# Extruder_1_Board.net
KiCad netlist of a schematic drawn in EAGLE
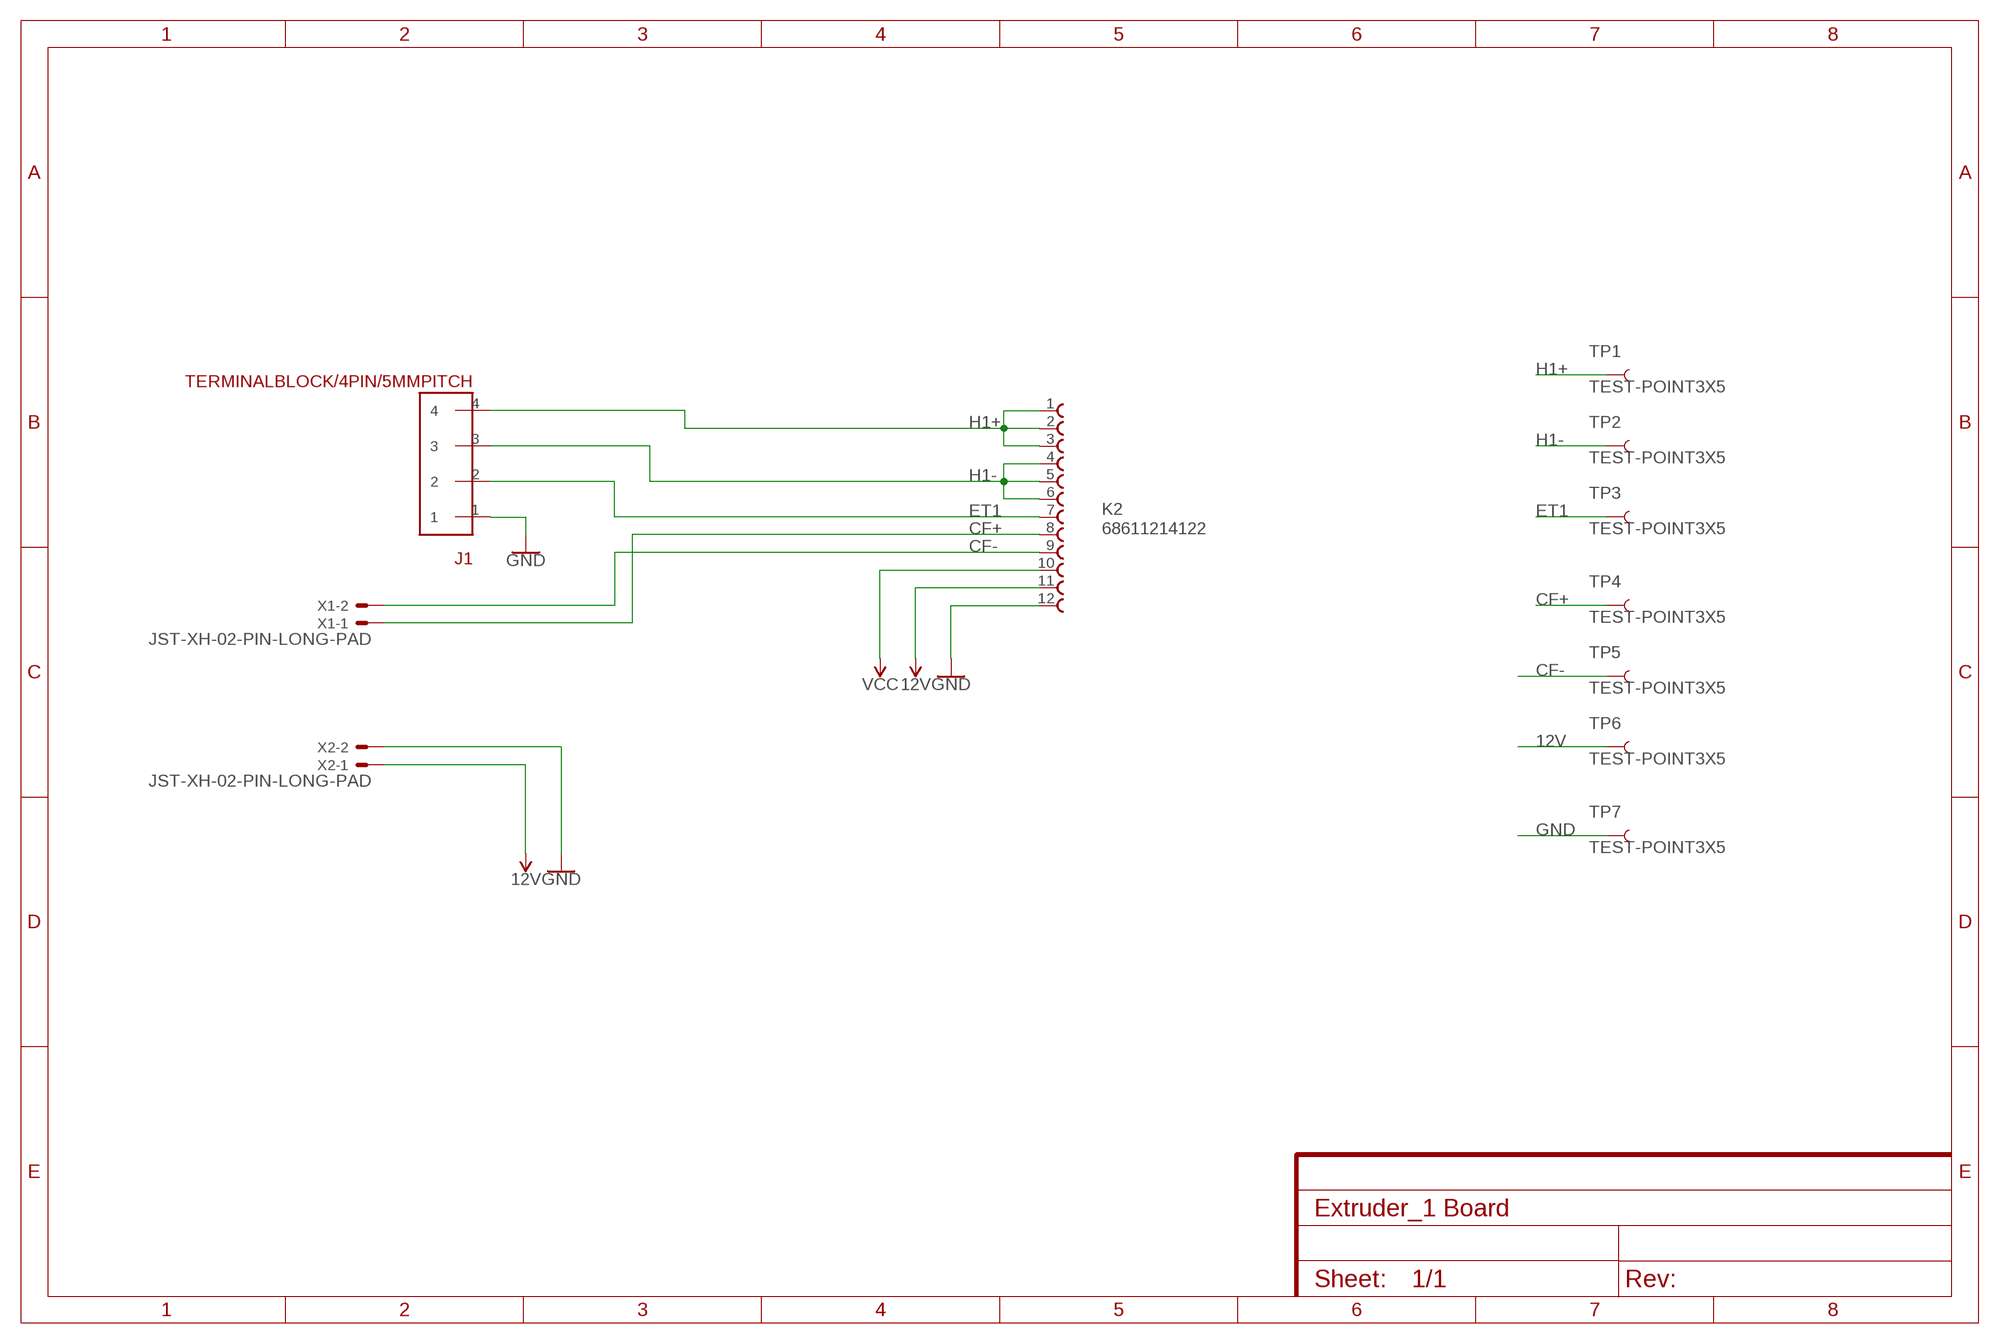
[diagram p0: schematic, sheet 1]

(export (version "E")
  (design (tool "Eeschema 10.0.6"))
  (components
    (comp (ref "J1")
      (value "TERMINALBLOCK/4PIN/5MMPITCH")
      (footprint "eagle-import:TERMINALBLOCK_TOYO_4PIN_5MMPITCH")
      (libsource (lib "eagle-import") (part "TERMINALBLOCK/4PIN/5MMPITCH"))
    )
    (comp (ref "K2")
      (value "68611214122")
      (footprint "eagle-import:68611214122")
      (libsource (lib "eagle-import") (part "68611214122"))
    )
    (comp (ref "TP1")
      (value "TEST-POINT3X5")
      (footprint "eagle-import:PAD.03X.05")
      (libsource (lib "eagle-import") (part "TEST-POINT3X5"))
    )
    (comp (ref "TP2")
      (value "TEST-POINT3X5")
      (footprint "eagle-import:PAD.03X.05")
      (libsource (lib "eagle-import") (part "TEST-POINT3X5"))
    )
    (comp (ref "TP3")
      (value "TEST-POINT3X5")
      (footprint "eagle-import:PAD.03X.05")
      (libsource (lib "eagle-import") (part "TEST-POINT3X5"))
    )
    (comp (ref "TP4")
      (value "TEST-POINT3X5")
      (footprint "eagle-import:PAD.03X.05")
      (libsource (lib "eagle-import") (part "TEST-POINT3X5"))
    )
    (comp (ref "TP5")
      (value "TEST-POINT3X5")
      (footprint "eagle-import:PAD.03X.05")
      (libsource (lib "eagle-import") (part "TEST-POINT3X5"))
    )
    (comp (ref "TP6")
      (value "TEST-POINT3X5")
      (footprint "eagle-import:PAD.03X.05")
      (libsource (lib "eagle-import") (part "TEST-POINT3X5"))
    )
    (comp (ref "TP7")
      (value "TEST-POINT3X5")
      (footprint "eagle-import:PAD.03X.05")
      (libsource (lib "eagle-import") (part "TEST-POINT3X5"))
    )
    (comp (ref "X1")
      (value "JST-XH-02-PIN-LONG-PAD")
      (footprint "eagle-import:JST-XH-02-PACKAGE-LONG-PAD")
      (libsource (lib "eagle-import") (part "JST-XH-02-PIN-LONG-PAD"))
    )
    (comp (ref "X2")
      (value "JST-XH-02-PIN-LONG-PAD")
      (footprint "eagle-import:JST-XH-02-PACKAGE-LONG-PAD")
      (libsource (lib "eagle-import") (part "JST-XH-02-PIN-LONG-PAD"))
    )
  )
  (nets
    (net (code "1") (name "/CF+") (class "Default")
      (node (ref "K2") (pin "8") (pinfunction "8_8") (pintype "passive"))
      (node (ref "TP4") (pin "P$1") (pinfunction "1_P$1") (pintype "bidirectional"))
      (node (ref "X1") (pin "1") (pinfunction "S_1") (pintype "passive"))
    )
    (net (code "2") (name "/CF-") (class "Default")
      (node (ref "K2") (pin "9") (pinfunction "9_9") (pintype "passive"))
      (node (ref "TP5") (pin "P$1") (pinfunction "1_P$1") (pintype "bidirectional"))
      (node (ref "X1") (pin "2") (pinfunction "S_2") (pintype "passive"))
    )
    (net (code "3") (name "/ET1") (class "Default")
      (node (ref "J1") (pin "2") (pinfunction "2_2") (pintype "bidirectional"))
      (node (ref "K2") (pin "7") (pinfunction "7_7") (pintype "passive"))
      (node (ref "TP3") (pin "P$1") (pinfunction "1_P$1") (pintype "bidirectional"))
    )
    (net (code "4") (name "/H1+") (class "Default")
      (node (ref "J1") (pin "4") (pinfunction "4_4") (pintype "bidirectional"))
      (node (ref "K2") (pin "1") (pinfunction "1_1") (pintype "passive"))
      (node (ref "K2") (pin "2") (pinfunction "2_2") (pintype "passive"))
      (node (ref "K2") (pin "3") (pinfunction "3_3") (pintype "passive"))
      (node (ref "TP1") (pin "P$1") (pinfunction "1_P$1") (pintype "bidirectional"))
    )
    (net (code "5") (name "/H1-") (class "Default")
      (node (ref "J1") (pin "3") (pinfunction "3_3") (pintype "bidirectional"))
      (node (ref "K2") (pin "4") (pinfunction "4_4") (pintype "passive"))
      (node (ref "K2") (pin "5") (pinfunction "5_5") (pintype "passive"))
      (node (ref "K2") (pin "6") (pinfunction "6_6") (pintype "passive"))
      (node (ref "TP2") (pin "P$1") (pinfunction "1_P$1") (pintype "bidirectional"))
    )
    (net (code "6") (name "12V") (class "Default")
      (node (ref "K2") (pin "11") (pinfunction "11_11") (pintype "passive"))
      (node (ref "TP6") (pin "P$1") (pinfunction "1_P$1") (pintype "bidirectional"))
      (node (ref "X2") (pin "1") (pinfunction "S_1") (pintype "passive"))
    )
    (net (code "7") (name "GND") (class "Default")
      (node (ref "J1") (pin "1") (pinfunction "1_1") (pintype "bidirectional"))
      (node (ref "K2") (pin "12") (pinfunction "12_12") (pintype "passive"))
      (node (ref "TP7") (pin "P$1") (pinfunction "1_P$1") (pintype "bidirectional"))
      (node (ref "X2") (pin "2") (pinfunction "S_2") (pintype "passive"))
    )
    (net (code "8") (name "VCC") (class "Default")
      (node (ref "K2") (pin "10") (pinfunction "10_10") (pintype "passive"))
    )
  )
)
